# Sheet3.net
KiCad netlist of a schematic drawn in Altium Designer
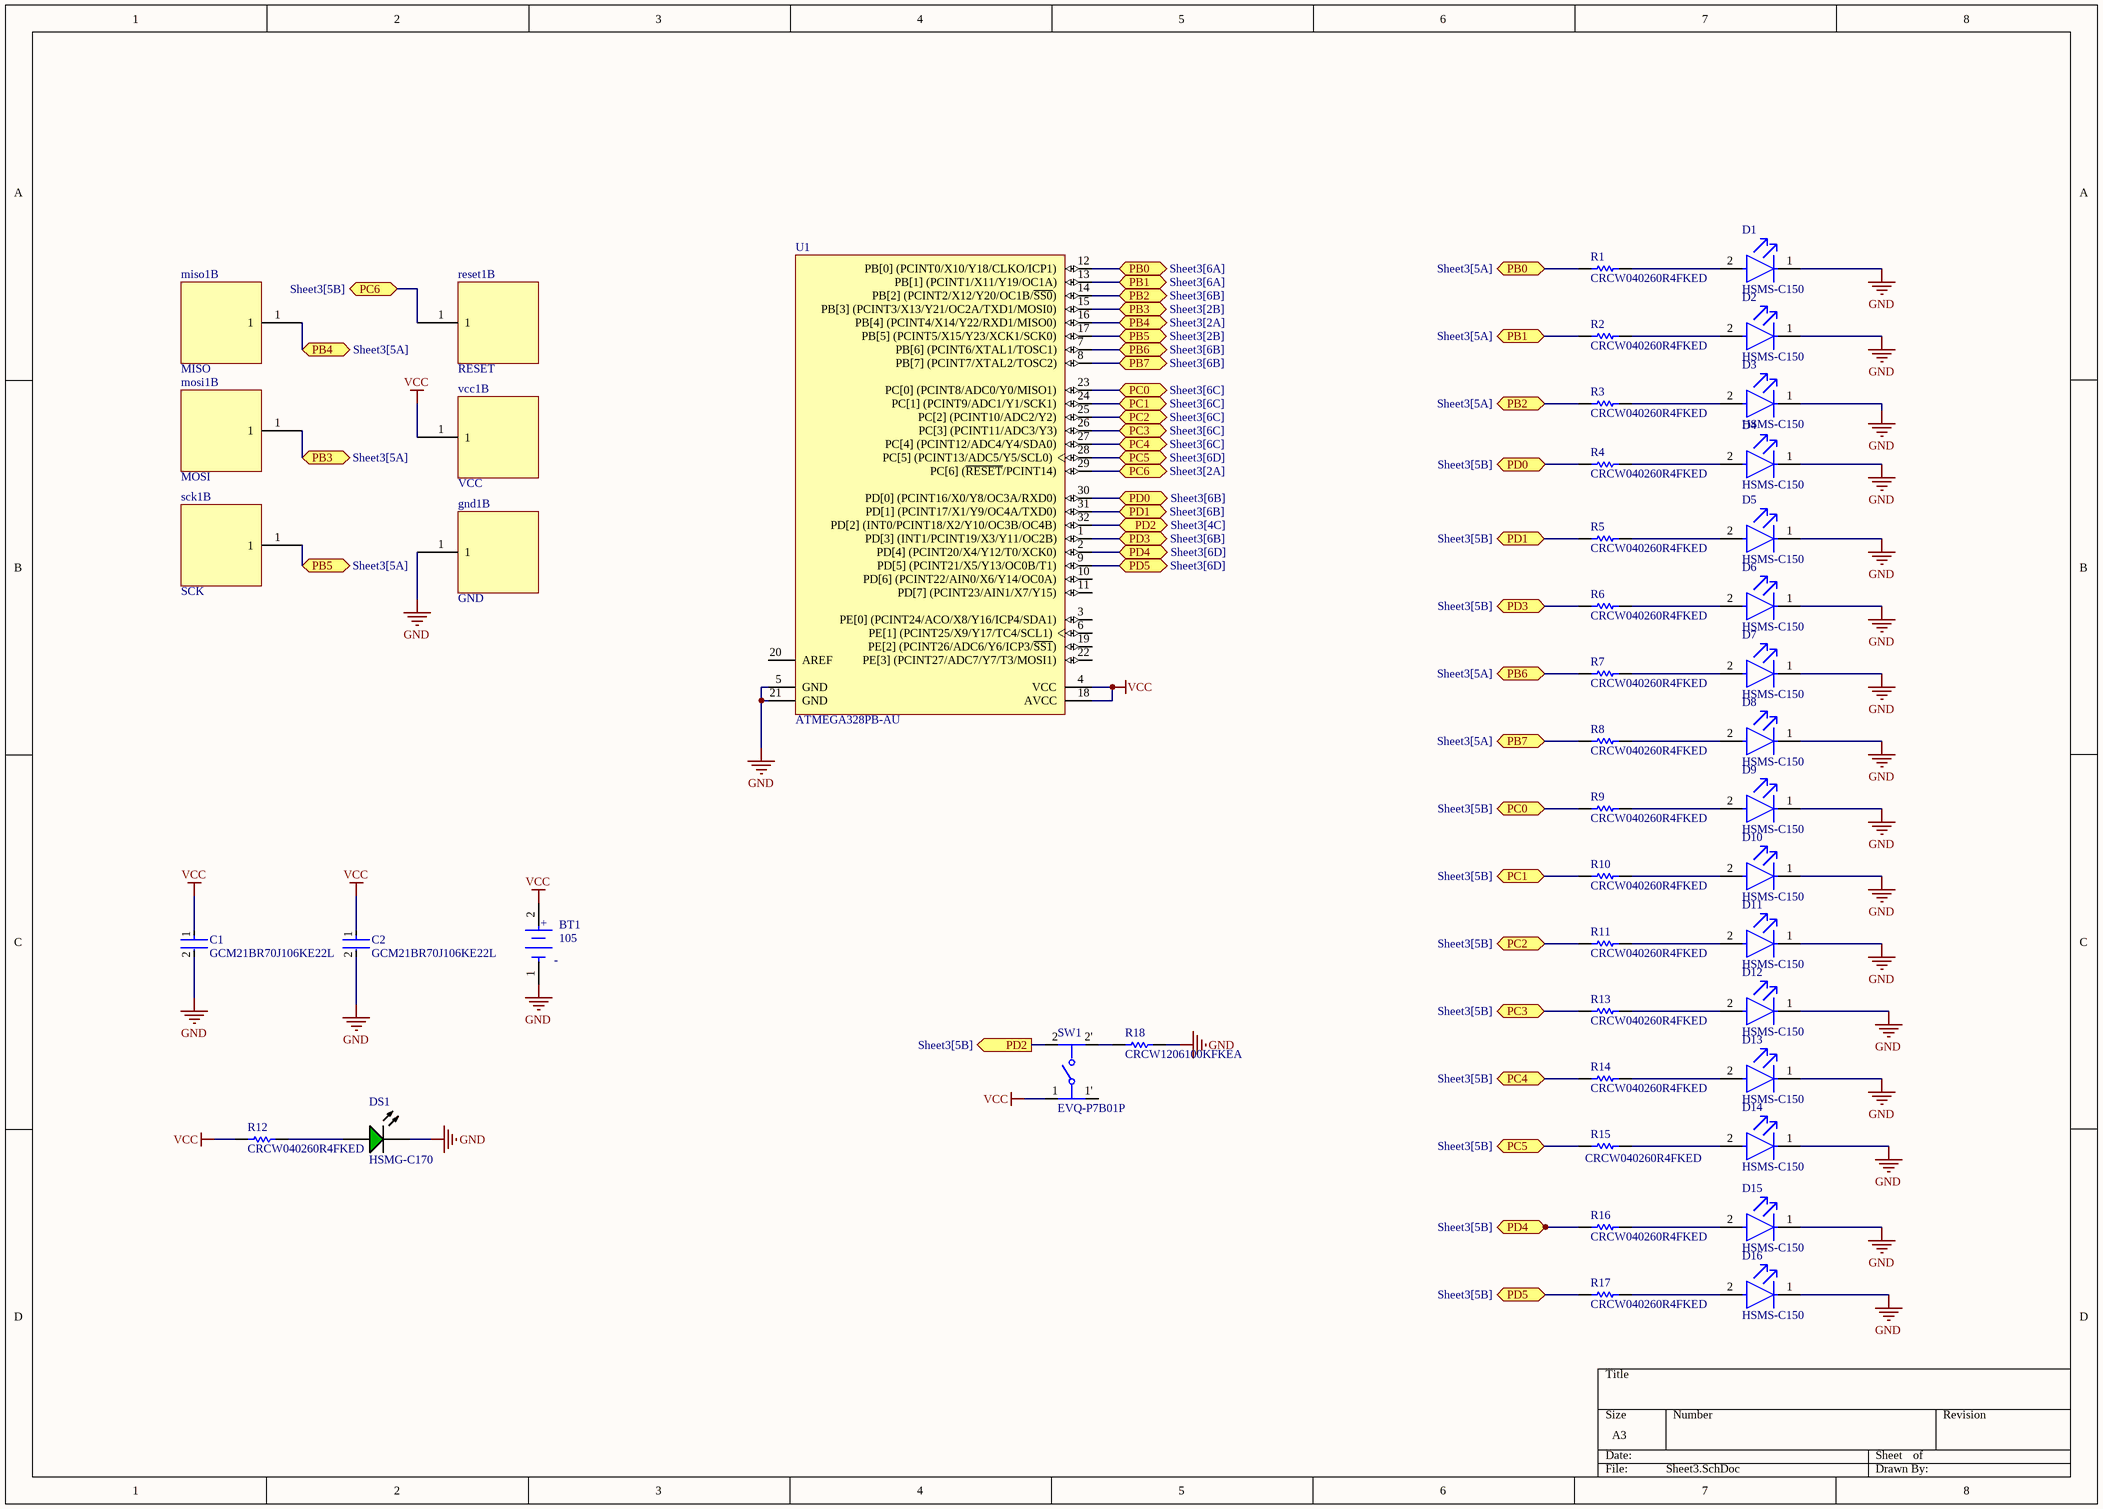
[diagram p0: Sheet3.SchDoc]

(export (version "E")
  (design (tool "Eeschema 10.0.6"))
  (components
    (comp (ref "BT1")
      (value "105")
      (footprint "FP-105-MFG")
      (description "105 Battery Holder Coin Cell 1 Cell PC Pin PCB Through Hole Mount PBT 0.944 in. Dia")
      (libsource (lib "Altium Content Vault") (part "db879b5662d49c975a5ff8b5862d222"))
    )
    (comp (ref "C1")
      (value "GCM21BR70J106KE22L")
      (footprint "FP-GCM21B-0_15-IPC_C")
      (description "Ceramic Capacitor for Automotive 10uF ±10% 6.3VDC X7R 0805 Embossed T/R")
      (fields (field (name "VOLTAGE") "6.3V") (field (name "TOLERANCE") "10%"))
      (libsource (lib "Altium Content Vault") (part "02cd4be3c70576c341d710602a673aa"))
    )
    (comp (ref "C2")
      (value "GCM21BR70J106KE22L")
      (footprint "FP-GCM21B-0_15-IPC_C")
      (description "Ceramic Capacitor for Automotive 10uF ±10% 6.3VDC X7R 0805 Embossed T/R")
      (fields (field (name "VOLTAGE") "6.3V") (field (name "TOLERANCE") "10%"))
      (libsource (lib "Altium Content Vault") (part "02cd4be3c70576c341d710602a673aa"))
    )
    (comp (ref "D1")
      (value "HSMS-C150")
      (footprint "FP-HSMS-C150-MFG")
      (description "LED RED DIFFUSED CHIP SMD")
      (libsource (lib "Altium Content Vault") (part "8706943c75ba83719d021d2fdc84c58"))
    )
    (comp (ref "D2")
      (value "HSMS-C150")
      (footprint "FP-HSMS-C150-MFG")
      (description "LED RED DIFFUSED CHIP SMD")
      (libsource (lib "Altium Content Vault") (part "8706943c75ba83719d021d2fdc84c58"))
    )
    (comp (ref "D3")
      (value "HSMS-C150")
      (footprint "FP-HSMS-C150-MFG")
      (description "LED RED DIFFUSED CHIP SMD")
      (libsource (lib "Altium Content Vault") (part "8706943c75ba83719d021d2fdc84c58"))
    )
    (comp (ref "D4")
      (value "HSMS-C150")
      (footprint "FP-HSMS-C150-MFG")
      (description "LED RED DIFFUSED CHIP SMD")
      (libsource (lib "Altium Content Vault") (part "8706943c75ba83719d021d2fdc84c58"))
    )
    (comp (ref "D5")
      (value "HSMS-C150")
      (footprint "FP-HSMS-C150-MFG")
      (description "LED RED DIFFUSED CHIP SMD")
      (libsource (lib "Altium Content Vault") (part "8706943c75ba83719d021d2fdc84c58"))
    )
    (comp (ref "D6")
      (value "HSMS-C150")
      (footprint "FP-HSMS-C150-MFG")
      (description "LED RED DIFFUSED CHIP SMD")
      (libsource (lib "Altium Content Vault") (part "8706943c75ba83719d021d2fdc84c58"))
    )
    (comp (ref "D7")
      (value "HSMS-C150")
      (footprint "FP-HSMS-C150-MFG")
      (description "LED RED DIFFUSED CHIP SMD")
      (libsource (lib "Altium Content Vault") (part "8706943c75ba83719d021d2fdc84c58"))
    )
    (comp (ref "D8")
      (value "HSMS-C150")
      (footprint "FP-HSMS-C150-MFG")
      (description "LED RED DIFFUSED CHIP SMD")
      (libsource (lib "Altium Content Vault") (part "8706943c75ba83719d021d2fdc84c58"))
    )
    (comp (ref "D9")
      (value "HSMS-C150")
      (footprint "FP-HSMS-C150-MFG")
      (description "LED RED DIFFUSED CHIP SMD")
      (libsource (lib "Altium Content Vault") (part "8706943c75ba83719d021d2fdc84c58"))
    )
    (comp (ref "D10")
      (value "HSMS-C150")
      (footprint "FP-HSMS-C150-MFG")
      (description "LED RED DIFFUSED CHIP SMD")
      (libsource (lib "Altium Content Vault") (part "8706943c75ba83719d021d2fdc84c58"))
    )
    (comp (ref "D11")
      (value "HSMS-C150")
      (footprint "FP-HSMS-C150-MFG")
      (description "LED RED DIFFUSED CHIP SMD")
      (libsource (lib "Altium Content Vault") (part "8706943c75ba83719d021d2fdc84c58"))
    )
    (comp (ref "D12")
      (value "HSMS-C150")
      (footprint "FP-HSMS-C150-MFG")
      (description "LED RED DIFFUSED CHIP SMD")
      (libsource (lib "Altium Content Vault") (part "8706943c75ba83719d021d2fdc84c58"))
    )
    (comp (ref "D13")
      (value "HSMS-C150")
      (footprint "FP-HSMS-C150-MFG")
      (description "LED RED DIFFUSED CHIP SMD")
      (libsource (lib "Altium Content Vault") (part "8706943c75ba83719d021d2fdc84c58"))
    )
    (comp (ref "D14")
      (value "HSMS-C150")
      (footprint "FP-HSMS-C150-MFG")
      (description "LED RED DIFFUSED CHIP SMD")
      (libsource (lib "Altium Content Vault") (part "8706943c75ba83719d021d2fdc84c58"))
    )
    (comp (ref "D15")
      (value "HSMS-C150")
      (footprint "FP-HSMS-C150-MFG")
      (description "LED RED DIFFUSED CHIP SMD")
      (libsource (lib "Altium Content Vault") (part "8706943c75ba83719d021d2fdc84c58"))
    )
    (comp (ref "D16")
      (value "HSMS-C150")
      (footprint "FP-HSMS-C150-MFG")
      (description "LED RED DIFFUSED CHIP SMD")
      (libsource (lib "Altium Content Vault") (part "8706943c75ba83719d021d2fdc84c58"))
    )
    (comp (ref "DS1")
      (value "HSMG-C170")
      (footprint "AVAG-HSMX-C170_V")
      (description "Chip LED, Green, 2.2 V, -40 to 85 degC, 2-Pin SMD, Pb-Free, Tape and Reel")
      (fields (field (name "MANUFACTURER") "Avago"))
      (libsource (lib "Altium Content Vault") (part "LED_GREEN_A1K2-2"))
    )
    (comp (ref "gnd1")
      (value "GND")
      (footprint "PCBComponent_1")
      (description "pad for pins")
      (libsource (lib "") (part "Component_1_1"))
    )
    (comp (ref "miso1")
      (value "MISO")
      (footprint "PCBComponent_1")
      (description "pad for pins")
      (libsource (lib "Schlib1") (part "Component_1"))
    )
    (comp (ref "mosi1")
      (value "MOSI")
      (footprint "PCBComponent_1")
      (description "pad for pins")
      (libsource (lib "Schlib1") (part "Component_1"))
    )
    (comp (ref "R1")
      (value "CRCW040260R4FKED")
      (footprint "RESC1005X40X25LL05T05")
      (fields (field (name "MANUFACTURER") "Vishay Dale"))
      (libsource (lib "Altium Content Vault") (part "RES"))
    )
    (comp (ref "R2")
      (value "CRCW040260R4FKED")
      (footprint "RESC1005X40X25LL05T05")
      (fields (field (name "MANUFACTURER") "Vishay Dale"))
      (libsource (lib "Altium Content Vault") (part "RES"))
    )
    (comp (ref "R3")
      (value "CRCW040260R4FKED")
      (footprint "RESC1005X40X25LL05T05")
      (fields (field (name "MANUFACTURER") "Vishay Dale"))
      (libsource (lib "Altium Content Vault") (part "RES"))
    )
    (comp (ref "R4")
      (value "CRCW040260R4FKED")
      (footprint "RESC1005X40X25LL05T05")
      (fields (field (name "MANUFACTURER") "Vishay Dale"))
      (libsource (lib "Altium Content Vault") (part "RES"))
    )
    (comp (ref "R5")
      (value "CRCW040260R4FKED")
      (footprint "RESC1005X40X25LL05T05")
      (fields (field (name "MANUFACTURER") "Vishay Dale"))
      (libsource (lib "Altium Content Vault") (part "RES"))
    )
    (comp (ref "R6")
      (value "CRCW040260R4FKED")
      (footprint "RESC1005X40X25LL05T05")
      (fields (field (name "MANUFACTURER") "Vishay Dale"))
      (libsource (lib "Altium Content Vault") (part "RES"))
    )
    (comp (ref "R7")
      (value "CRCW040260R4FKED")
      (footprint "RESC1005X40X25LL05T05")
      (fields (field (name "MANUFACTURER") "Vishay Dale"))
      (libsource (lib "Altium Content Vault") (part "RES"))
    )
    (comp (ref "R8")
      (value "CRCW040260R4FKED")
      (footprint "RESC1005X40X25LL05T05")
      (fields (field (name "MANUFACTURER") "Vishay Dale"))
      (libsource (lib "Altium Content Vault") (part "RES"))
    )
    (comp (ref "R9")
      (value "CRCW040260R4FKED")
      (footprint "RESC1005X40X25LL05T05")
      (fields (field (name "MANUFACTURER") "Vishay Dale"))
      (libsource (lib "Altium Content Vault") (part "RES"))
    )
    (comp (ref "R10")
      (value "CRCW040260R4FKED")
      (footprint "RESC1005X40X25LL05T05")
      (fields (field (name "MANUFACTURER") "Vishay Dale"))
      (libsource (lib "Altium Content Vault") (part "RES"))
    )
    (comp (ref "R11")
      (value "CRCW040260R4FKED")
      (footprint "RESC1005X40X25LL05T05")
      (fields (field (name "MANUFACTURER") "Vishay Dale"))
      (libsource (lib "Altium Content Vault") (part "RES"))
    )
    (comp (ref "R12")
      (value "CRCW040260R4FKED")
      (footprint "RESC1005X40X25LL05T05")
      (fields (field (name "MANUFACTURER") "Vishay Dale"))
      (libsource (lib "Altium Content Vault") (part "RES"))
    )
    (comp (ref "R13")
      (value "CRCW040260R4FKED")
      (footprint "RESC1005X40X25LL05T05")
      (fields (field (name "MANUFACTURER") "Vishay Dale"))
      (libsource (lib "Altium Content Vault") (part "RES"))
    )
    (comp (ref "R14")
      (value "CRCW040260R4FKED")
      (footprint "RESC1005X40X25LL05T05")
      (fields (field (name "MANUFACTURER") "Vishay Dale"))
      (libsource (lib "Altium Content Vault") (part "RES"))
    )
    (comp (ref "R15")
      (value "CRCW040260R4FKED")
      (footprint "RESC1005X40X25LL05T05")
      (fields (field (name "MANUFACTURER") "Vishay Dale"))
      (libsource (lib "Altium Content Vault") (part "RES"))
    )
    (comp (ref "R16")
      (value "CRCW040260R4FKED")
      (footprint "RESC1005X40X25LL05T05")
      (fields (field (name "MANUFACTURER") "Vishay Dale"))
      (libsource (lib "Altium Content Vault") (part "RES"))
    )
    (comp (ref "R17")
      (value "CRCW040260R4FKED")
      (footprint "RESC1005X40X25LL05T05")
      (fields (field (name "MANUFACTURER") "Vishay Dale"))
      (libsource (lib "Altium Content Vault") (part "RES"))
    )
    (comp (ref "R18")
      (value "CRCW1206100KFKEA")
      (footprint "RESC3216X60X45NL10T20")
      (fields (field (name "MANUFACTURER") "Vishay Dale"))
      (libsource (lib "Altium Content Vault") (part "RES"))
    )
    (comp (ref "reset1")
      (value "RESET")
      (footprint "PCBComponent_1")
      (description "pad for pins")
      (libsource (lib "") (part "Component_1_1"))
    )
    (comp (ref "sck1")
      (value "SCK")
      (footprint "PCBComponent_1")
      (description "pad for pins")
      (libsource (lib "Schlib1") (part "Component_1"))
    )
    (comp (ref "SW1")
      (value "EVQ-P7B01P")
      (footprint "FP-EVQ-P7B01P-MFG")
      (description "SWITCH TACTILE SPST-NO 0.05A 12V")
      (libsource (lib "Altium Content Vault") (part "210e32ac5400ec01d635f9bada53656"))
    )
    (comp (ref "U1")
      (value "ATMEGA328PB-AU")
      (footprint "ATML-32A_L")
      (fields (field (name "MANUFACTURER") "Microchip"))
      (libsource (lib "Altium Content Vault") (part "ATML-ATMEGA328PB-32A"))
    )
    (comp (ref "vcc1")
      (value "VCC")
      (footprint "PCBComponent_1")
      (description "pad for pins")
      (libsource (lib "") (part "Component_1_1"))
    )
  )
  (nets
    (net (code "1") (name "/PB0") (class "Default")
      (node (ref "R1") (pin "1") (pinfunction "1_1") (pintype "passive"))
      (node (ref "U1") (pin "12") (pinfunction "PB[0]_(PCINT0/X10/Y18/CLKO/ICP1)_12") (pintype "bidirectional"))
    )
    (net (code "2") (name "/PB1") (class "Default")
      (node (ref "R2") (pin "1") (pinfunction "1_1") (pintype "passive"))
      (node (ref "U1") (pin "13") (pinfunction "PB[1]_(PCINT1/X11/Y19/OC1A)_13") (pintype "bidirectional"))
    )
    (net (code "3") (name "/PB2") (class "Default")
      (node (ref "R3") (pin "1") (pinfunction "1_1") (pintype "passive"))
      (node (ref "U1") (pin "14") (pinfunction "PB[2]_(PCINT2/X12/Y20/OC1B/~{SS0})_14") (pintype "bidirectional"))
    )
    (net (code "4") (name "/PB3") (class "Default")
      (node (ref "U1") (pin "15") (pinfunction "PB[3]_(PCINT3/X13/Y21/OC2A/TXD1/MOSI0)_15") (pintype "bidirectional"))
      (node (ref "mosi1") (pin "1") (pinfunction "1_1") (pintype "passive"))
    )
    (net (code "5") (name "/PB4") (class "Default")
      (node (ref "U1") (pin "16") (pinfunction "PB[4]_(PCINT4/X14/Y22/RXD1/MISO0)_16") (pintype "bidirectional"))
      (node (ref "miso1") (pin "1") (pinfunction "1_1") (pintype "passive"))
    )
    (net (code "6") (name "/PB5") (class "Default")
      (node (ref "U1") (pin "17") (pinfunction "PB[5]_(PCINT5/X15/Y23/XCK1/SCK0)_17") (pintype "bidirectional"))
      (node (ref "sck1") (pin "1") (pinfunction "1_1") (pintype "passive"))
    )
    (net (code "7") (name "/PB6") (class "Default")
      (node (ref "R7") (pin "1") (pinfunction "1_1") (pintype "passive"))
      (node (ref "U1") (pin "7") (pinfunction "PB[6]_(PCINT6/XTAL1/TOSC1)_7") (pintype "bidirectional"))
    )
    (net (code "8") (name "/PB7") (class "Default")
      (node (ref "R8") (pin "1") (pinfunction "1_1") (pintype "passive"))
      (node (ref "U1") (pin "8") (pinfunction "PB[7]_(PCINT7/XTAL2/TOSC2)_8") (pintype "bidirectional"))
    )
    (net (code "9") (name "/PC0") (class "Default")
      (node (ref "R9") (pin "1") (pinfunction "1_1") (pintype "passive"))
      (node (ref "U1") (pin "23") (pinfunction "PC[0]_(PCINT8/ADC0/Y0/MISO1)_23") (pintype "bidirectional"))
    )
    (net (code "10") (name "/PC1") (class "Default")
      (node (ref "R10") (pin "1") (pinfunction "1_1") (pintype "passive"))
      (node (ref "U1") (pin "24") (pinfunction "PC[1]_(PCINT9/ADC1/Y1/SCK1)_24") (pintype "bidirectional"))
    )
    (net (code "11") (name "/PC2") (class "Default")
      (node (ref "R11") (pin "1") (pinfunction "1_1") (pintype "passive"))
      (node (ref "U1") (pin "25") (pinfunction "PC[2]_(PCINT10/ADC2/Y2)_25") (pintype "bidirectional"))
    )
    (net (code "12") (name "/PC3") (class "Default")
      (node (ref "R13") (pin "1") (pinfunction "1_1") (pintype "passive"))
      (node (ref "U1") (pin "26") (pinfunction "PC[3]_(PCINT11/ADC3/Y3)_26") (pintype "bidirectional"))
    )
    (net (code "13") (name "/PC4") (class "Default")
      (node (ref "R14") (pin "1") (pinfunction "1_1") (pintype "passive"))
      (node (ref "U1") (pin "27") (pinfunction "PC[4]_(PCINT12/ADC4/Y4/SDA0)_27") (pintype "bidirectional"))
    )
    (net (code "14") (name "/PC5") (class "Default")
      (node (ref "R15") (pin "1") (pinfunction "1_1") (pintype "passive"))
      (node (ref "U1") (pin "28") (pinfunction "PC[5]_(PCINT13/ADC5/Y5/SCL0)_28") (pintype "bidirectional"))
    )
    (net (code "15") (name "/PC6") (class "Default")
      (node (ref "U1") (pin "29") (pinfunction "PC[6]_(~{RESET}/PCINT14)_29") (pintype "bidirectional"))
      (node (ref "reset1") (pin "1") (pinfunction "1_1") (pintype "passive"))
    )
    (net (code "16") (name "/PD0") (class "Default")
      (node (ref "R4") (pin "1") (pinfunction "1_1") (pintype "passive"))
      (node (ref "U1") (pin "30") (pinfunction "PD[0]_(PCINT16/X0/Y8/OC3A/RXD0)_30") (pintype "bidirectional"))
    )
    (net (code "17") (name "/PD1") (class "Default")
      (node (ref "R5") (pin "1") (pinfunction "1_1") (pintype "passive"))
      (node (ref "U1") (pin "31") (pinfunction "PD[1]_(PCINT17/X1/Y9/OC4A/TXD0)_31") (pintype "bidirectional"))
    )
    (net (code "18") (name "/PD2") (class "Default")
      (node (ref "SW1") (pin "2") (pinfunction "2_2") (pintype "passive"))
      (node (ref "U1") (pin "32") (pinfunction "PD[2]_(INT0/PCINT18/X2/Y10/OC3B/OC4B)_32") (pintype "bidirectional"))
    )
    (net (code "19") (name "/PD3") (class "Default")
      (node (ref "R6") (pin "1") (pinfunction "1_1") (pintype "passive"))
      (node (ref "U1") (pin "1") (pinfunction "PD[3]_(INT1/PCINT19/X3/Y11/OC2B)_1") (pintype "bidirectional"))
    )
    (net (code "20") (name "/PD4") (class "Default")
      (node (ref "R16") (pin "1") (pinfunction "1_1") (pintype "passive"))
      (node (ref "U1") (pin "2") (pinfunction "PD[4]_(PCINT20/X4/Y12/T0/XCK0)_2") (pintype "bidirectional"))
    )
    (net (code "21") (name "/PD5") (class "Default")
      (node (ref "R17") (pin "1") (pinfunction "1_1") (pintype "passive"))
      (node (ref "U1") (pin "9") (pinfunction "PD[5]_(PCINT21/X5/Y13/OC0B/T1)_9") (pintype "bidirectional"))
    )
    (net (code "22") (name "GND") (class "Default")
      (node (ref "BT1") (pin "1") (pinfunction "-_1") (pintype "passive"))
      (node (ref "C1") (pin "2") (pinfunction "2_2") (pintype "passive"))
      (node (ref "C2") (pin "2") (pinfunction "2_2") (pintype "passive"))
      (node (ref "D1") (pin "1") (pinfunction "C_1") (pintype "passive"))
      (node (ref "D10") (pin "1") (pinfunction "C_1") (pintype "passive"))
      (node (ref "D11") (pin "1") (pinfunction "C_1") (pintype "passive"))
      (node (ref "D12") (pin "1") (pinfunction "C_1") (pintype "passive"))
      (node (ref "D13") (pin "1") (pinfunction "C_1") (pintype "passive"))
      (node (ref "D14") (pin "1") (pinfunction "C_1") (pintype "passive"))
      (node (ref "D15") (pin "1") (pinfunction "C_1") (pintype "passive"))
      (node (ref "D16") (pin "1") (pinfunction "C_1") (pintype "passive"))
      (node (ref "D2") (pin "1") (pinfunction "C_1") (pintype "passive"))
      (node (ref "D3") (pin "1") (pinfunction "C_1") (pintype "passive"))
      (node (ref "D4") (pin "1") (pinfunction "C_1") (pintype "passive"))
      (node (ref "D5") (pin "1") (pinfunction "C_1") (pintype "passive"))
      (node (ref "D6") (pin "1") (pinfunction "C_1") (pintype "passive"))
      (node (ref "D7") (pin "1") (pinfunction "C_1") (pintype "passive"))
      (node (ref "D8") (pin "1") (pinfunction "C_1") (pintype "passive"))
      (node (ref "D9") (pin "1") (pinfunction "C_1") (pintype "passive"))
      (node (ref "DS1") (pin "2") (pinfunction "K_2") (pintype "passive"))
      (node (ref "R18") (pin "1") (pinfunction "1_1") (pintype "passive"))
      (node (ref "U1") (pin "21") (pinfunction "GND_21") (pintype "power_in"))
      (node (ref "U1") (pin "5") (pinfunction "GND_5") (pintype "power_in"))
      (node (ref "gnd1") (pin "1") (pinfunction "1_1") (pintype "passive"))
    )
    (net (code "23") (name "Net-(D1-A)") (class "Default")
      (node (ref "D1") (pin "2") (pinfunction "A_2") (pintype "passive"))
      (node (ref "R1") (pin "2") (pinfunction "2_2") (pintype "passive"))
    )
    (net (code "24") (name "Net-(D2-A)") (class "Default")
      (node (ref "D2") (pin "2") (pinfunction "A_2") (pintype "passive"))
      (node (ref "R2") (pin "2") (pinfunction "2_2") (pintype "passive"))
    )
    (net (code "25") (name "Net-(D3-A)") (class "Default")
      (node (ref "D3") (pin "2") (pinfunction "A_2") (pintype "passive"))
      (node (ref "R3") (pin "2") (pinfunction "2_2") (pintype "passive"))
    )
    (net (code "26") (name "Net-(D4-A)") (class "Default")
      (node (ref "D4") (pin "2") (pinfunction "A_2") (pintype "passive"))
      (node (ref "R4") (pin "2") (pinfunction "2_2") (pintype "passive"))
    )
    (net (code "27") (name "Net-(D5-A)") (class "Default")
      (node (ref "D5") (pin "2") (pinfunction "A_2") (pintype "passive"))
      (node (ref "R5") (pin "2") (pinfunction "2_2") (pintype "passive"))
    )
    (net (code "28") (name "Net-(D6-A)") (class "Default")
      (node (ref "D6") (pin "2") (pinfunction "A_2") (pintype "passive"))
      (node (ref "R6") (pin "2") (pinfunction "2_2") (pintype "passive"))
    )
    (net (code "29") (name "Net-(D7-A)") (class "Default")
      (node (ref "D7") (pin "2") (pinfunction "A_2") (pintype "passive"))
      (node (ref "R7") (pin "2") (pinfunction "2_2") (pintype "passive"))
    )
    (net (code "30") (name "Net-(D8-A)") (class "Default")
      (node (ref "D8") (pin "2") (pinfunction "A_2") (pintype "passive"))
      (node (ref "R8") (pin "2") (pinfunction "2_2") (pintype "passive"))
    )
    (net (code "31") (name "Net-(D9-A)") (class "Default")
      (node (ref "D9") (pin "2") (pinfunction "A_2") (pintype "passive"))
      (node (ref "R9") (pin "2") (pinfunction "2_2") (pintype "passive"))
    )
    (net (code "32") (name "Net-(D10-A)") (class "Default")
      (node (ref "D10") (pin "2") (pinfunction "A_2") (pintype "passive"))
      (node (ref "R10") (pin "2") (pinfunction "2_2") (pintype "passive"))
    )
    (net (code "33") (name "Net-(D11-A)") (class "Default")
      (node (ref "D11") (pin "2") (pinfunction "A_2") (pintype "passive"))
      (node (ref "R11") (pin "2") (pinfunction "2_2") (pintype "passive"))
    )
    (net (code "34") (name "Net-(D12-A)") (class "Default")
      (node (ref "D12") (pin "2") (pinfunction "A_2") (pintype "passive"))
      (node (ref "R13") (pin "2") (pinfunction "2_2") (pintype "passive"))
    )
    (net (code "35") (name "Net-(D13-A)") (class "Default")
      (node (ref "D13") (pin "2") (pinfunction "A_2") (pintype "passive"))
      (node (ref "R14") (pin "2") (pinfunction "2_2") (pintype "passive"))
    )
    (net (code "36") (name "Net-(D14-A)") (class "Default")
      (node (ref "D14") (pin "2") (pinfunction "A_2") (pintype "passive"))
      (node (ref "R15") (pin "2") (pinfunction "2_2") (pintype "passive"))
    )
    (net (code "37") (name "Net-(D15-A)") (class "Default")
      (node (ref "D15") (pin "2") (pinfunction "A_2") (pintype "passive"))
      (node (ref "R16") (pin "2") (pinfunction "2_2") (pintype "passive"))
    )
    (net (code "38") (name "Net-(D16-A)") (class "Default")
      (node (ref "D16") (pin "2") (pinfunction "A_2") (pintype "passive"))
      (node (ref "R17") (pin "2") (pinfunction "2_2") (pintype "passive"))
    )
    (net (code "39") (name "Net-(DS1-A)") (class "Default")
      (node (ref "DS1") (pin "1") (pinfunction "A_1") (pintype "passive"))
      (node (ref "R12") (pin "2") (pinfunction "2_2") (pintype "passive"))
    )
    (net (code "40") (name "Net-(R18-Pad2)") (class "Default")
      (node (ref "R18") (pin "2") (pinfunction "2_2") (pintype "passive"))
      (node (ref "SW1") (pin "2'") (pinfunction "2'_2'") (pintype "passive"))
    )
    (net (code "41") (name "VCC") (class "Default")
      (node (ref "BT1") (pin "2") (pinfunction "+_2") (pintype "passive"))
      (node (ref "C1") (pin "1") (pinfunction "1_1") (pintype "passive"))
      (node (ref "C2") (pin "1") (pinfunction "1_1") (pintype "passive"))
      (node (ref "R12") (pin "1") (pinfunction "1_1") (pintype "passive"))
      (node (ref "SW1") (pin "1") (pinfunction "1_1") (pintype "passive"))
      (node (ref "U1") (pin "18") (pinfunction "AVCC_18") (pintype "power_in"))
      (node (ref "U1") (pin "4") (pinfunction "VCC_4") (pintype "power_in"))
      (node (ref "vcc1") (pin "1") (pinfunction "1_1") (pintype "passive"))
    )
    (net (code "42") (name "unconnected-(SW1-Pad1')") (class "Default")
      (node (ref "SW1") (pin "1'") (pinfunction "1'_1'") (pintype "passive"))
    )
    (net (code "43") (name "unconnected-(U1-AREF-Pad20)") (class "Default")
      (node (ref "U1") (pin "20") (pinfunction "AREF_20") (pintype "passive"))
    )
    (net (code "44") (name "unconnected-(U1-PD[6]_(PCINT22{slash}AIN0{slash}X6{slash}Y14{slash}OC0A)-Pad10)") (class "Default")
      (node (ref "U1") (pin "10") (pinfunction "PD[6]_(PCINT22/AIN0/X6/Y14/OC0A)_10") (pintype "bidirectional"))
    )
    (net (code "45") (name "unconnected-(U1-PD[7]_(PCINT23{slash}AIN1{slash}X7{slash}Y15)-Pad11)") (class "Default")
      (node (ref "U1") (pin "11") (pinfunction "PD[7]_(PCINT23/AIN1/X7/Y15)_11") (pintype "bidirectional"))
    )
    (net (code "46") (name "unconnected-(U1-PE[0]_(PCINT24{slash}ACO{slash}X8{slash}Y16{slash}ICP4{slash}SDA1)-Pad3)") (class "Default")
      (node (ref "U1") (pin "3") (pinfunction "PE[0]_(PCINT24/ACO/X8/Y16/ICP4/SDA1)_3") (pintype "bidirectional"))
    )
    (net (code "47") (name "unconnected-(U1-PE[1]_(PCINT25{slash}X9{slash}Y17{slash}TC4{slash}SCL1)-Pad6)") (class "Default")
      (node (ref "U1") (pin "6") (pinfunction "PE[1]_(PCINT25/X9/Y17/TC4/SCL1)_6") (pintype "bidirectional"))
    )
    (net (code "48") (name "unconnected-(U1-PE[2]_(PCINT26{slash}ADC6{slash}Y6{slash}ICP3{slash}~{SS1})-Pad19)") (class "Default")
      (node (ref "U1") (pin "19") (pinfunction "PE[2]_(PCINT26/ADC6/Y6/ICP3/~{SS1})_19") (pintype "bidirectional"))
    )
    (net (code "49") (name "unconnected-(U1-PE[3]_(PCINT27{slash}ADC7{slash}Y7{slash}T3{slash}MOSI1)-Pad22)") (class "Default")
      (node (ref "U1") (pin "22") (pinfunction "PE[3]_(PCINT27/ADC7/Y7/T3/MOSI1)_22") (pintype "bidirectional"))
    )
  )
)
